# base2.net
KiCad netlist of a schematic drawn in EAGLE
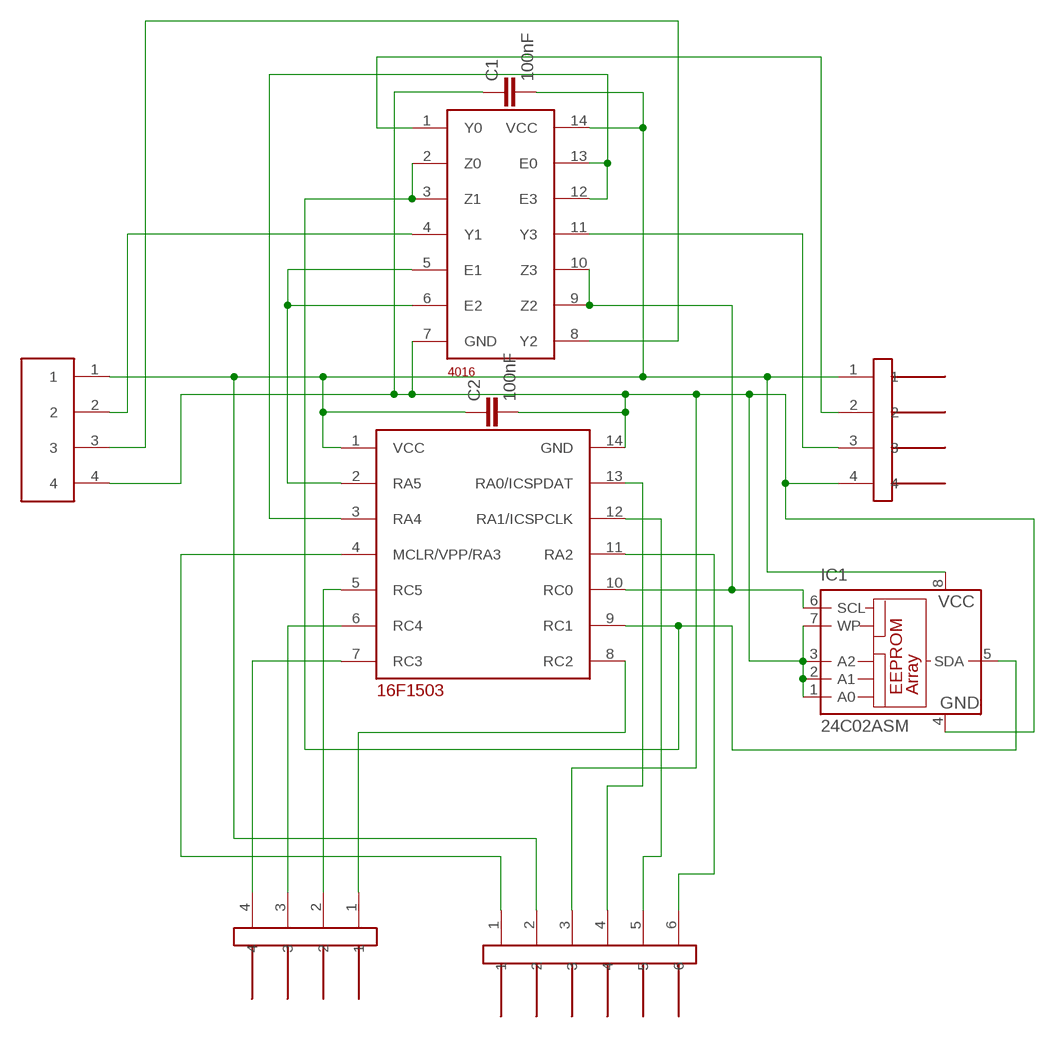
[diagram p0: schematic, sheet 1]

(export (version "E")
  (design (tool "Eeschema 10.0.6"))
  (components
    (comp (ref "C1")
      (value "100nF")
      (footprint "eagle-import:C0805")
      (libsource (lib "eagle-import") (part "C-EUC0805"))
    )
    (comp (ref "C2")
      (value "100nF")
      (footprint "eagle-import:C0805")
      (libsource (lib "eagle-import") (part "C-EUC0805"))
    )
    (comp (ref "IC1")
      (value "24C02ASM")
      (footprint "eagle-import:SO-08M")
      (fields (field (name "MF") "MICROCHIP") (field (name "MPN") "24C02C/SN"))
      (libsource (lib "eagle-import") (part "24SMC02A"))
    )
    (comp (ref "INPUT")
      (value "JUMPER4")
      (footprint "eagle-import:JUMPER4")
      (libsource (lib "eagle-import") (part "JUMPER4"))
    )
    (comp (ref "IO")
      (value "JUMPER4M")
      (footprint "eagle-import:JUMPER4M")
      (libsource (lib "eagle-import") (part "JUMPER4M"))
    )
    (comp (ref "OUTPUT")
      (value "JUMPER4F")
      (footprint "eagle-import:JUMPER4F")
      (libsource (lib "eagle-import") (part "JUMPER4F"))
    )
    (comp (ref "PROGRAMMER")
      (value "JUMPER6M")
      (footprint "eagle-import:JUMPER6M")
      (libsource (lib "eagle-import") (part "JUMPER6M"))
    )
    (comp (ref "U$1")
      (value "16F1503")
      (footprint "eagle-import:16F1503")
      (libsource (lib "eagle-import") (part "16F1503"))
    )
    (comp (ref "U$2")
      (value "4016")
      (footprint "eagle-import:SO14")
      (libsource (lib "eagle-import") (part "4016"))
    )
  )
  (nets
    (net (code "1") (name "Net-(IC1-A0)") (class "Default")
      (node (ref "C1") (pin "1") (pinfunction "1_1") (pintype "passive"))
      (node (ref "C2") (pin "2") (pinfunction "2_2") (pintype "passive"))
      (node (ref "IC1") (pin "1") (pinfunction "A0_1") (pintype "input"))
      (node (ref "IC1") (pin "2") (pinfunction "A1_2") (pintype "input"))
      (node (ref "IC1") (pin "3") (pinfunction "A2_3") (pintype "input"))
      (node (ref "IC1") (pin "4") (pinfunction "GND_4") (pintype "power_in"))
      (node (ref "IC1") (pin "7") (pinfunction "WP_7") (pintype "input"))
      (node (ref "INPUT") (pin "4") (pinfunction "4_4") (pintype "bidirectional"))
      (node (ref "OUTPUT") (pin "4") (pinfunction "4_4") (pintype "bidirectional"))
      (node (ref "PROGRAMMER") (pin "3") (pinfunction "3_3") (pintype "bidirectional"))
      (node (ref "U$1") (pin "14") (pinfunction "GND_14") (pintype "power_in"))
      (node (ref "U$2") (pin "7") (pinfunction "GND_7") (pintype "bidirectional"))
    )
    (net (code "2") (name "Net-(IC1-SCL)") (class "Default")
      (node (ref "IC1") (pin "6") (pinfunction "SCL_6") (pintype "input"))
      (node (ref "U$1") (pin "10") (pinfunction "RC0_10") (pintype "bidirectional"))
      (node (ref "U$2") (pin "10") (pinfunction "Z3_10") (pintype "bidirectional"))
      (node (ref "U$2") (pin "9") (pinfunction "Z2_9") (pintype "bidirectional"))
    )
    (net (code "3") (name "Net-(IC1-SDA)") (class "Default")
      (node (ref "IC1") (pin "5") (pinfunction "SDA_5") (pintype "bidirectional"))
      (node (ref "U$1") (pin "9") (pinfunction "RC1_9") (pintype "bidirectional"))
      (node (ref "U$2") (pin "2") (pinfunction "Z0_2") (pintype "bidirectional"))
      (node (ref "U$2") (pin "3") (pinfunction "Z1_3") (pintype "bidirectional"))
    )
    (net (code "4") (name "Net-(IC1-VCC)") (class "Default")
      (node (ref "C1") (pin "2") (pinfunction "2_2") (pintype "passive"))
      (node (ref "C2") (pin "1") (pinfunction "1_1") (pintype "passive"))
      (node (ref "IC1") (pin "8") (pinfunction "VCC_8") (pintype "power_in"))
      (node (ref "INPUT") (pin "1") (pinfunction "1_1") (pintype "bidirectional"))
      (node (ref "OUTPUT") (pin "1") (pinfunction "1_1") (pintype "bidirectional"))
      (node (ref "PROGRAMMER") (pin "2") (pinfunction "2_2") (pintype "bidirectional"))
      (node (ref "U$1") (pin "1") (pinfunction "VCC_1") (pintype "power_in"))
      (node (ref "U$2") (pin "14") (pinfunction "VCC_14") (pintype "bidirectional"))
    )
    (net (code "5") (name "Net-(U$1-MCLR{slash}VPP{slash}RA3)") (class "Default")
      (node (ref "PROGRAMMER") (pin "1") (pinfunction "1_1") (pintype "bidirectional"))
      (node (ref "U$1") (pin "4") (pinfunction "MCLR/VPP/RA3_4") (pintype "bidirectional"))
    )
    (net (code "6") (name "Net-(U$1-RA0{slash}ICSPDAT)") (class "Default")
      (node (ref "PROGRAMMER") (pin "4") (pinfunction "4_4") (pintype "bidirectional"))
      (node (ref "U$1") (pin "13") (pinfunction "RA0/ICSPDAT_13") (pintype "bidirectional"))
    )
    (net (code "7") (name "Net-(U$1-RA1{slash}ICSPCLK)") (class "Default")
      (node (ref "PROGRAMMER") (pin "5") (pinfunction "5_5") (pintype "bidirectional"))
      (node (ref "U$1") (pin "12") (pinfunction "RA1/ICSPCLK_12") (pintype "bidirectional"))
    )
    (net (code "8") (name "Net-(U$1-RA2)") (class "Default")
      (node (ref "PROGRAMMER") (pin "6") (pinfunction "6_6") (pintype "bidirectional"))
      (node (ref "U$1") (pin "11") (pinfunction "RA2_11") (pintype "bidirectional"))
    )
    (net (code "9") (name "Net-(U$1-RA4)") (class "Default")
      (node (ref "U$1") (pin "3") (pinfunction "RA4_3") (pintype "bidirectional"))
      (node (ref "U$2") (pin "12") (pinfunction "E3_12") (pintype "bidirectional"))
      (node (ref "U$2") (pin "13") (pinfunction "E0_13") (pintype "bidirectional"))
    )
    (net (code "10") (name "Net-(U$1-RA5)") (class "Default")
      (node (ref "U$1") (pin "2") (pinfunction "RA5_2") (pintype "bidirectional"))
      (node (ref "U$2") (pin "5") (pinfunction "E1_5") (pintype "bidirectional"))
      (node (ref "U$2") (pin "6") (pinfunction "E2_6") (pintype "bidirectional"))
    )
    (net (code "11") (name "Net-(U$1-RC2)") (class "Default")
      (node (ref "IO") (pin "1") (pinfunction "1_1") (pintype "bidirectional"))
      (node (ref "U$1") (pin "8") (pinfunction "RC2_8") (pintype "bidirectional"))
    )
    (net (code "12") (name "Net-(U$1-RC3)") (class "Default")
      (node (ref "IO") (pin "4") (pinfunction "4_4") (pintype "bidirectional"))
      (node (ref "U$1") (pin "7") (pinfunction "RC3_7") (pintype "bidirectional"))
    )
    (net (code "13") (name "Net-(U$1-RC4)") (class "Default")
      (node (ref "IO") (pin "3") (pinfunction "3_3") (pintype "bidirectional"))
      (node (ref "U$1") (pin "6") (pinfunction "RC4_6") (pintype "bidirectional"))
    )
    (net (code "14") (name "Net-(U$1-RC5)") (class "Default")
      (node (ref "IO") (pin "2") (pinfunction "2_2") (pintype "bidirectional"))
      (node (ref "U$1") (pin "5") (pinfunction "RC5_5") (pintype "bidirectional"))
    )
    (net (code "15") (name "Net-(U$2-Y0)") (class "Default")
      (node (ref "INPUT") (pin "2") (pinfunction "2_2") (pintype "bidirectional"))
      (node (ref "U$2") (pin "1") (pinfunction "Y0_1") (pintype "bidirectional"))
    )
    (net (code "16") (name "Net-(U$2-Y1)") (class "Default")
      (node (ref "OUTPUT") (pin "2") (pinfunction "2_2") (pintype "bidirectional"))
      (node (ref "U$2") (pin "4") (pinfunction "Y1_4") (pintype "bidirectional"))
    )
    (net (code "17") (name "Net-(U$2-Y2)") (class "Default")
      (node (ref "OUTPUT") (pin "3") (pinfunction "3_3") (pintype "bidirectional"))
      (node (ref "U$2") (pin "8") (pinfunction "Y2_8") (pintype "bidirectional"))
    )
    (net (code "18") (name "Net-(U$2-Y3)") (class "Default")
      (node (ref "INPUT") (pin "3") (pinfunction "3_3") (pintype "bidirectional"))
      (node (ref "U$2") (pin "11") (pinfunction "Y3_11") (pintype "bidirectional"))
    )
  )
)
